# Boost_Converter.net
KiCad netlist of a schematic drawn in Altium Designer
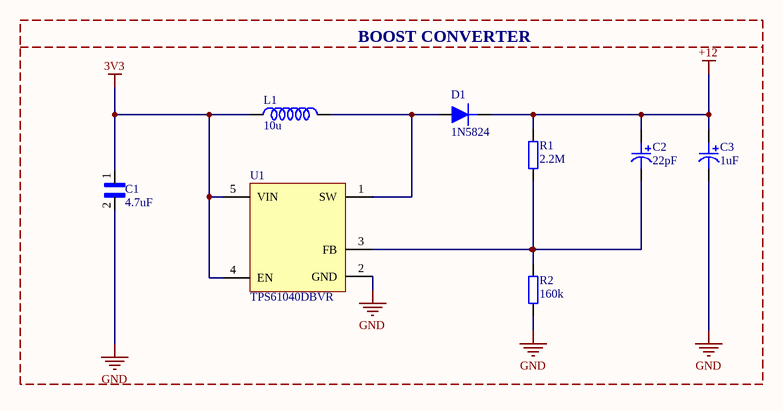
[diagram p0: Boost_Converter.SchDoc]

(export (version "E")
  (design (tool "Eeschema 10.0.6"))
  (components
    (comp (ref "C1")
      (value "4.7uF")
      (footprint "CAP-0805-NP0")
      (description "Cap Ceramic 0.01uF 50V C0G 5% Pad SMD 0805 125°C T/R")
      (fields
        (field (name "MANUFACTURER") "Yageo")
        (field (name "MANUFACTURER PART NUMBER") "CC0805JKNPO9BN103")
        (field (name "DESIGNER") "ZehraOzkan")
      )
      (libsource (lib "Schematic-Lib-Zhrzkn") (part "CAP-0805-NP0-10nF"))
    )
    (comp (ref "C2")
      (value "22pF")
      (footprint "F981C475MMA")
      (description "Cap Tant Solid 4.7uF 16V M CASE 20%( 1.6 X 0.85 X 0.8mm) Inward L SMD 12 Ohm 125C T/R")
      (fields
        (field (name "MANUFACTURER") "Kyocera AVX")
        (field (name "MANUFACTURER PART NUMBER") "F981C475MMA")
      )
      (libsource (lib "Schematic-Lib-Zhrzkn") (part "CAP_0603_16V_Tantalum"))
    )
    (comp (ref "C3")
      (value "1uF")
      (footprint "F981C475MMA")
      (description "Cap Tant Solid 4.7uF 16V M CASE 20%( 1.6 X 0.85 X 0.8mm) Inward L SMD 12 Ohm 125C T/R")
      (fields
        (field (name "MANUFACTURER") "Kyocera AVX")
        (field (name "MANUFACTURER PART NUMBER") "F981C475MMA")
      )
      (libsource (lib "Schematic-Lib-Zhrzkn") (part "CAP_0603_16V_Tantalum"))
    )
    (comp (ref "D1")
      (value "1N5824")
      (footprint "SOD323F")
      (description "Diode Schottky 30V 5A 2-Pin Axial Leaded Tray")
      (fields (field (name "MANUFACTURER") "Microsemi") (field (name "DESIGNER") "ZehraOzkan"))
      (libsource (lib "Schematic-Lib-Zhrzkn") (part "1N5824"))
    )
    (comp (ref "L1")
      (value "10u")
      (footprint "IND_1212")
      (description "Fixed Ind 47UH 390MA 2.3 Ohm SMD")
      (fields
        (field (name "MANUFACTURER") "Wurth Electronics")
        (field (name "MANUFACTURER PART NUMBER") "78438335470")
        (field (name "DESIGNER") "ZehraOzkan")
      )
      (libsource (lib "Schematic-Lib-Zhrzkn") (part "IND_47uH"))
    )
    (comp (ref "R1")
      (value "2.2M")
      (footprint "RES_0603")
      (description "Resistor SMD 0603")
      (libsource (lib "Schematic-Lib-Zhrzkn") (part "RES_0603"))
    )
    (comp (ref "R2")
      (value "160k")
      (footprint "RES_0603")
      (description "Resistor SMD 0603")
      (libsource (lib "Schematic-Lib-Zhrzkn") (part "RES_0603"))
    )
    (comp (ref "U1")
      (value "TPS61040DBVR")
      (footprint "SOT-23-5")
      (description "Conv DC-DC 1.8V to 6V Step Up Single-Out 1.8V to 28V 0.4A 5-Pin SOT-23 T/R")
      (fields (field (name "MANUFACTURER") "Texas Instruments"))
      (libsource (lib "Schematic-Lib-Zhrzkn") (part "TPS61040DBVR"))
    )
  )
  (nets
    (net (code "1") (name "+12") (class "Default")
      (node (ref "C2") (pin "1") (pinfunction "1_1") (pintype "passive"))
      (node (ref "C3") (pin "1") (pinfunction "1_1") (pintype "passive"))
      (node (ref "D1") (pin "2") (pinfunction "K_2") (pintype "passive"))
      (node (ref "R1") (pin "2") (pinfunction "2_2") (pintype "passive"))
    )
    (net (code "2") (name "3V3") (class "Default")
      (node (ref "C1") (pin "1") (pinfunction "1_1") (pintype "passive"))
      (node (ref "L1") (pin "1") (pinfunction "1_1") (pintype "passive"))
      (node (ref "U1") (pin "4") (pinfunction "EN_4") (pintype "passive"))
      (node (ref "U1") (pin "5") (pinfunction "VIN_5") (pintype "passive"))
    )
    (net (code "3") (name "GND") (class "Default")
      (node (ref "C1") (pin "2") (pinfunction "2_2") (pintype "passive"))
      (node (ref "C3") (pin "2") (pinfunction "2_2") (pintype "passive"))
      (node (ref "R2") (pin "1") (pinfunction "1_1") (pintype "passive"))
      (node (ref "U1") (pin "2") (pinfunction "GND_2") (pintype "passive"))
    )
    (net (code "4") (name "Net-(D1-A)") (class "Default")
      (node (ref "D1") (pin "1") (pinfunction "A_1") (pintype "passive"))
      (node (ref "L1") (pin "2") (pinfunction "2_2") (pintype "passive"))
      (node (ref "U1") (pin "1") (pinfunction "SW_1") (pintype "power_in"))
    )
    (net (code "5") (name "Net-(U1-FB)") (class "Default")
      (node (ref "C2") (pin "2") (pinfunction "2_2") (pintype "passive"))
      (node (ref "R1") (pin "1") (pinfunction "1_1") (pintype "passive"))
      (node (ref "R2") (pin "2") (pinfunction "2_2") (pintype "passive"))
      (node (ref "U1") (pin "3") (pinfunction "FB_3") (pintype "passive"))
    )
  )
)
